# Transceivers.net
KiCad netlist of a schematic drawn in Altium Designer
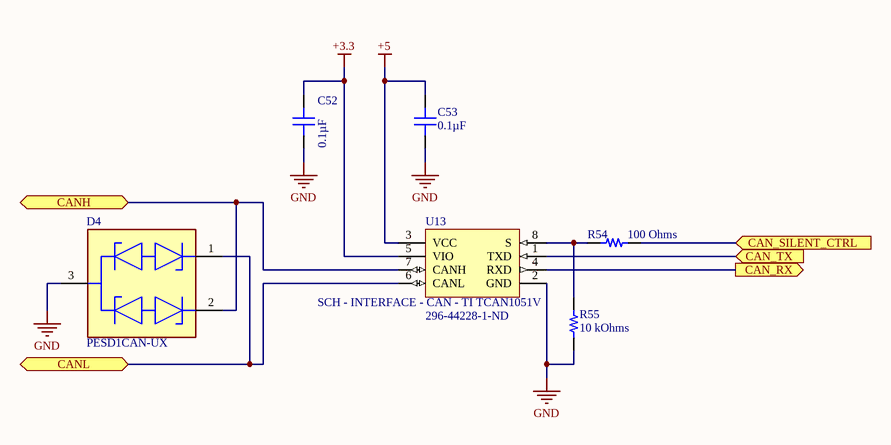
[diagram p0: Transceivers.SchDoc]

(export (version "E")
  (design (tool "Eeschema 10.0.6"))
  (components
    (comp (ref "C52")
      (value "0.1µF")
      (footprint "CAP 0603_1608")
      (description "CAP CER 0.1UF 25V X7R 0603")
      (fields
        (field (name "PART NUMBER") "CL10B104KA8WPNC")
        (field (name "MANUFACTURER") "Samsung Electro-Mechanics")
      )
      (libsource (lib "Celestial Altium Library - altium_library") (part "Capacitor"))
    )
    (comp (ref "C53")
      (value "0.1µF")
      (footprint "CAP 0603_1608")
      (description "CAP CER 0.1UF 25V X7R 0603")
      (fields
        (field (name "PART NUMBER") "CL10B104KA8WPNC")
        (field (name "MANUFACTURER") "Samsung Electro-Mechanics")
      )
      (libsource (lib "Celestial Altium Library - altium_library") (part "Capacitor"))
    )
    (comp (ref "D4")
      (value "PESD1CAN-UX")
      (footprint "FP-SOT323-MFG")
      (description "TVS DIODE 24V 50V SC70-3")
      (libsource (lib "Altium Content Vault") (part "04d57993b6b7b0f5b3c95ba4f97dea0"))
    )
    (comp (ref "R54")
      (value "100 Ohms")
      (footprint "RES 0603_1608")
      (description "RES 100 OHM 1% 1/10W 0603")
      (fields
        (field (name "PART NUMBER") "RMCF0603FG100R")
        (field (name "MANUFACTURER") "Stackpole Electronics Inc")
      )
      (libsource (lib "Celestial Altium Library - altium_library") (part "Resistor"))
    )
    (comp (ref "R55")
      (value "10 kOhms")
      (footprint "RES 0603_1608")
      (description "RES 10K OHM 5% 1/10W 0603")
      (fields
        (field (name "PART NUMBER") "RMCF0603JT10K0")
        (field (name "MANUFACTURER") "Stackpole Electronics Inc")
      )
      (libsource (lib "Celestial Altium Library - altium_library") (part "Resistor"))
    )
    (comp (ref "U13")
      (value "SCH - INTERFACE - CAN - TI TCAN1051V")
      (footprint "PCB - LEADS - SOIC - TI SOIC-8")
      (fields (field (name "SUPPLIER PART NUMBER 1") "296-44228-1-ND"))
      (libsource (lib "HAB_ICs") (part "SCH - INTERFACE - CAN - TI TCAN1051V"))
    )
  )
  (nets
    (net (code "1") (name "+3.3") (class "Default")
      (node (ref "C52") (pin "2") (pinfunction "2_2") (pintype "passive"))
      (node (ref "U13") (pin "5") (pinfunction "VIO_5") (pintype "power_in"))
    )
    (net (code "2") (name "+5") (class "Default")
      (node (ref "C53") (pin "2") (pinfunction "2_2") (pintype "passive"))
      (node (ref "U13") (pin "3") (pinfunction "VCC_3") (pintype "power_in"))
    )
    (net (code "3") (name "/CANH") (class "Default")
      (node (ref "D4") (pin "2") (pinfunction "cathode_2_2") (pintype "passive"))
      (node (ref "U13") (pin "7") (pinfunction "CANH_7") (pintype "bidirectional"))
    )
    (net (code "4") (name "/CANL") (class "Default")
      (node (ref "D4") (pin "1") (pinfunction "cathode_1_1") (pintype "passive"))
      (node (ref "U13") (pin "6") (pinfunction "CANL_6") (pintype "bidirectional"))
    )
    (net (code "5") (name "/CAN_RX") (class "Default")
      (node (ref "U13") (pin "4") (pinfunction "RXD_4") (pintype "output"))
    )
    (net (code "6") (name "/CAN_SILENT_CTRL") (class "Default")
      (node (ref "R54") (pin "2") (pinfunction "2_2") (pintype "passive"))
    )
    (net (code "7") (name "/CAN_TX") (class "Default")
      (node (ref "U13") (pin "1") (pinfunction "TXD_1") (pintype "input"))
    )
    (net (code "8") (name "GND") (class "Default")
      (node (ref "C52") (pin "1") (pinfunction "1_1") (pintype "passive"))
      (node (ref "C53") (pin "1") (pinfunction "1_1") (pintype "passive"))
      (node (ref "D4") (pin "3") (pinfunction "common_cathode_3") (pintype "passive"))
      (node (ref "R55") (pin "1") (pinfunction "1_1") (pintype "passive"))
      (node (ref "U13") (pin "2") (pinfunction "GND_2") (pintype "power_in"))
    )
    (net (code "9") (name "Net-(U13-S)") (class "Default")
      (node (ref "R54") (pin "1") (pinfunction "1_1") (pintype "passive"))
      (node (ref "R55") (pin "2") (pinfunction "2_2") (pintype "passive"))
      (node (ref "U13") (pin "8") (pinfunction "S_8") (pintype "input"))
    )
  )
)
